# TTN-Node-v7-01.net
KiCad netlist of a schematic drawn in EAGLE
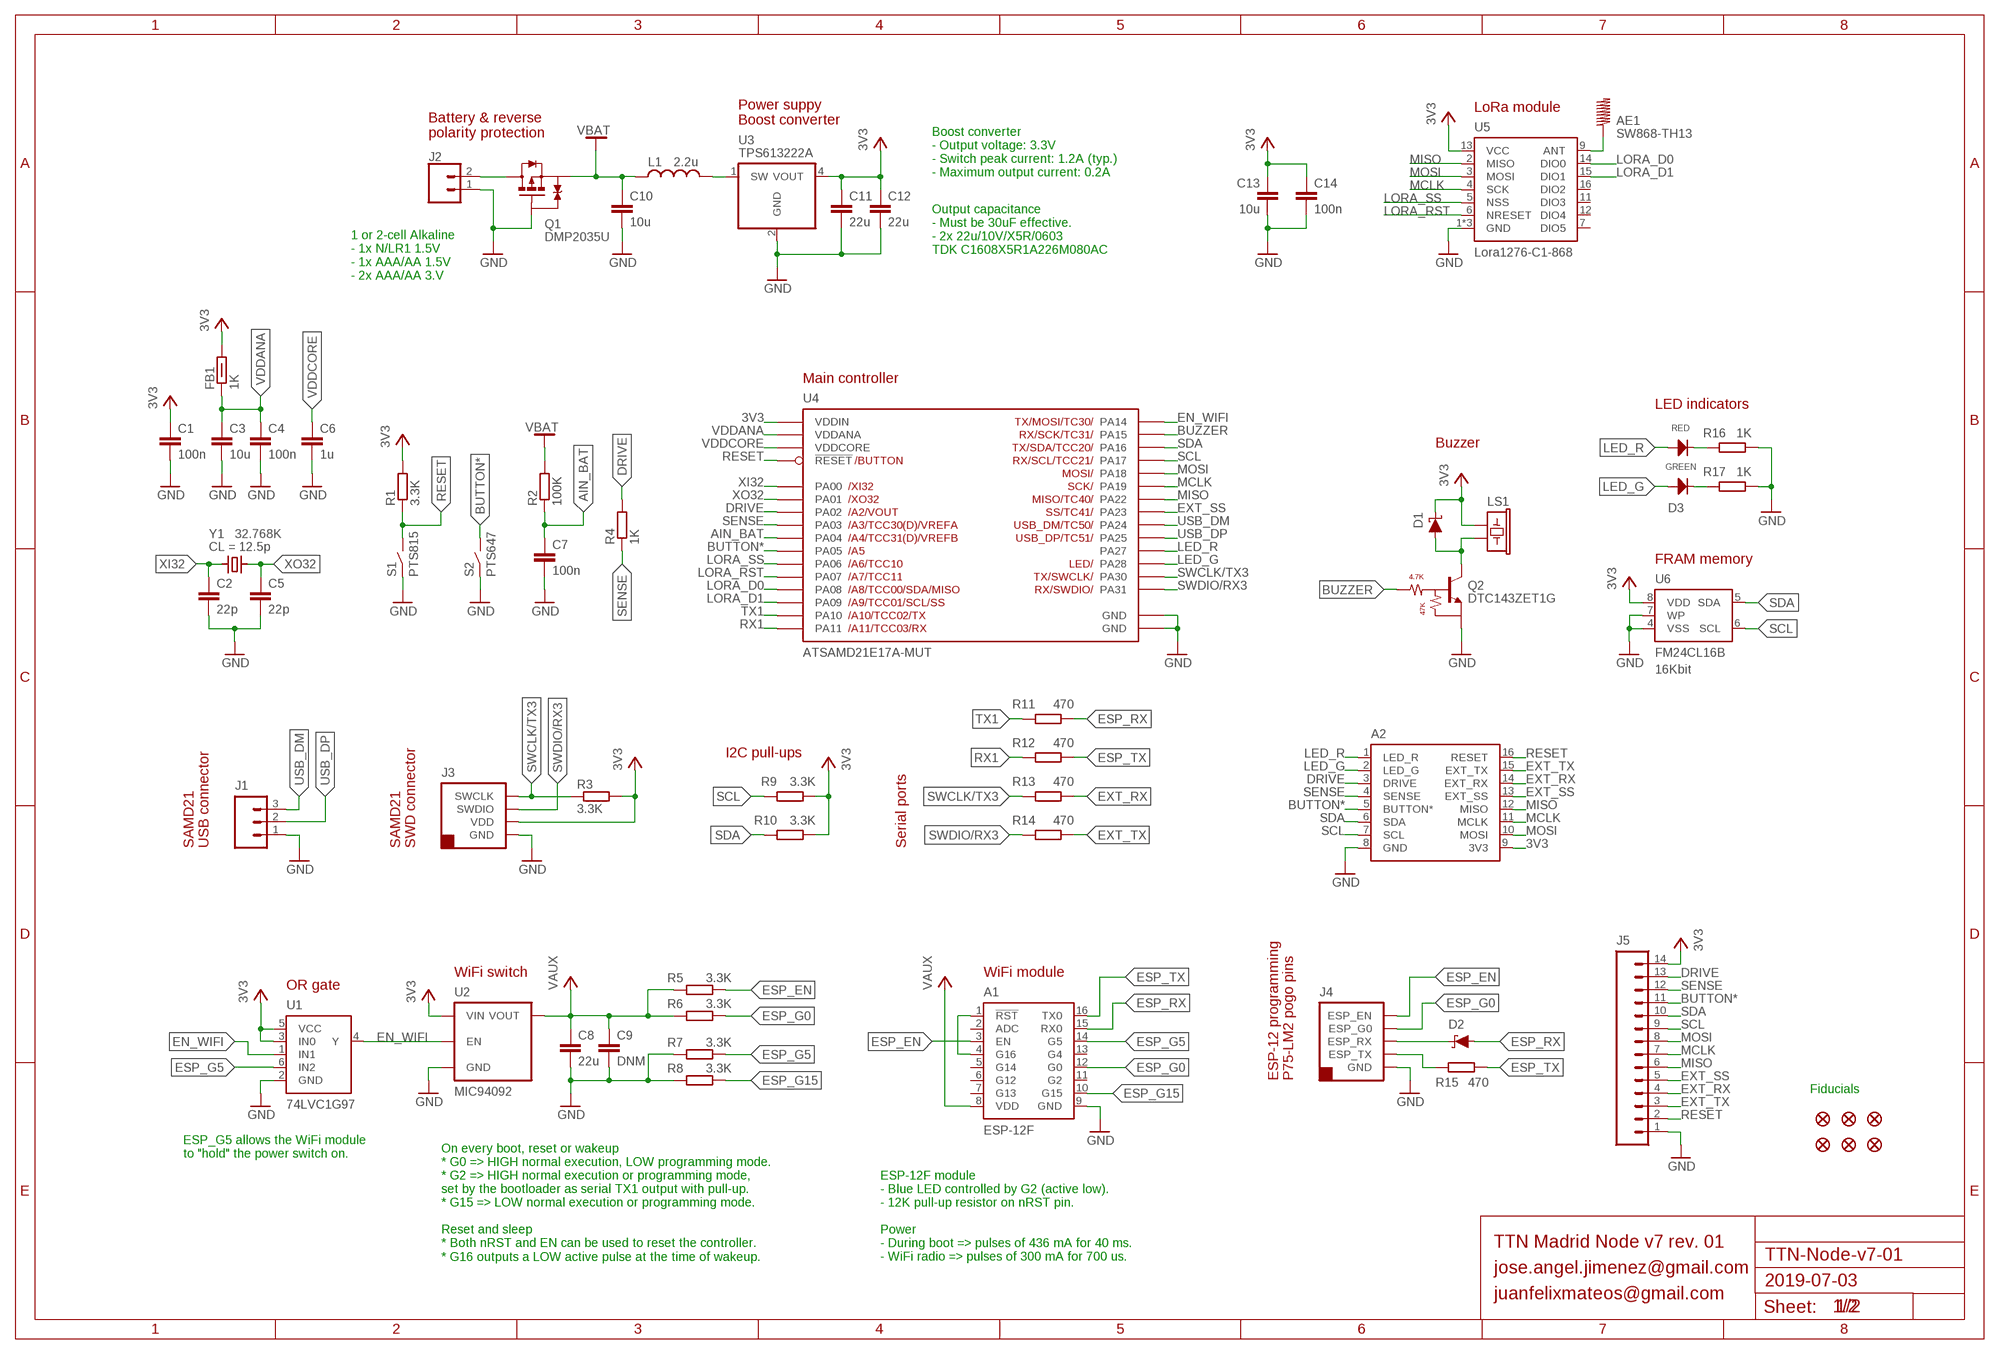
[diagram p0: schematic, sheet 1]
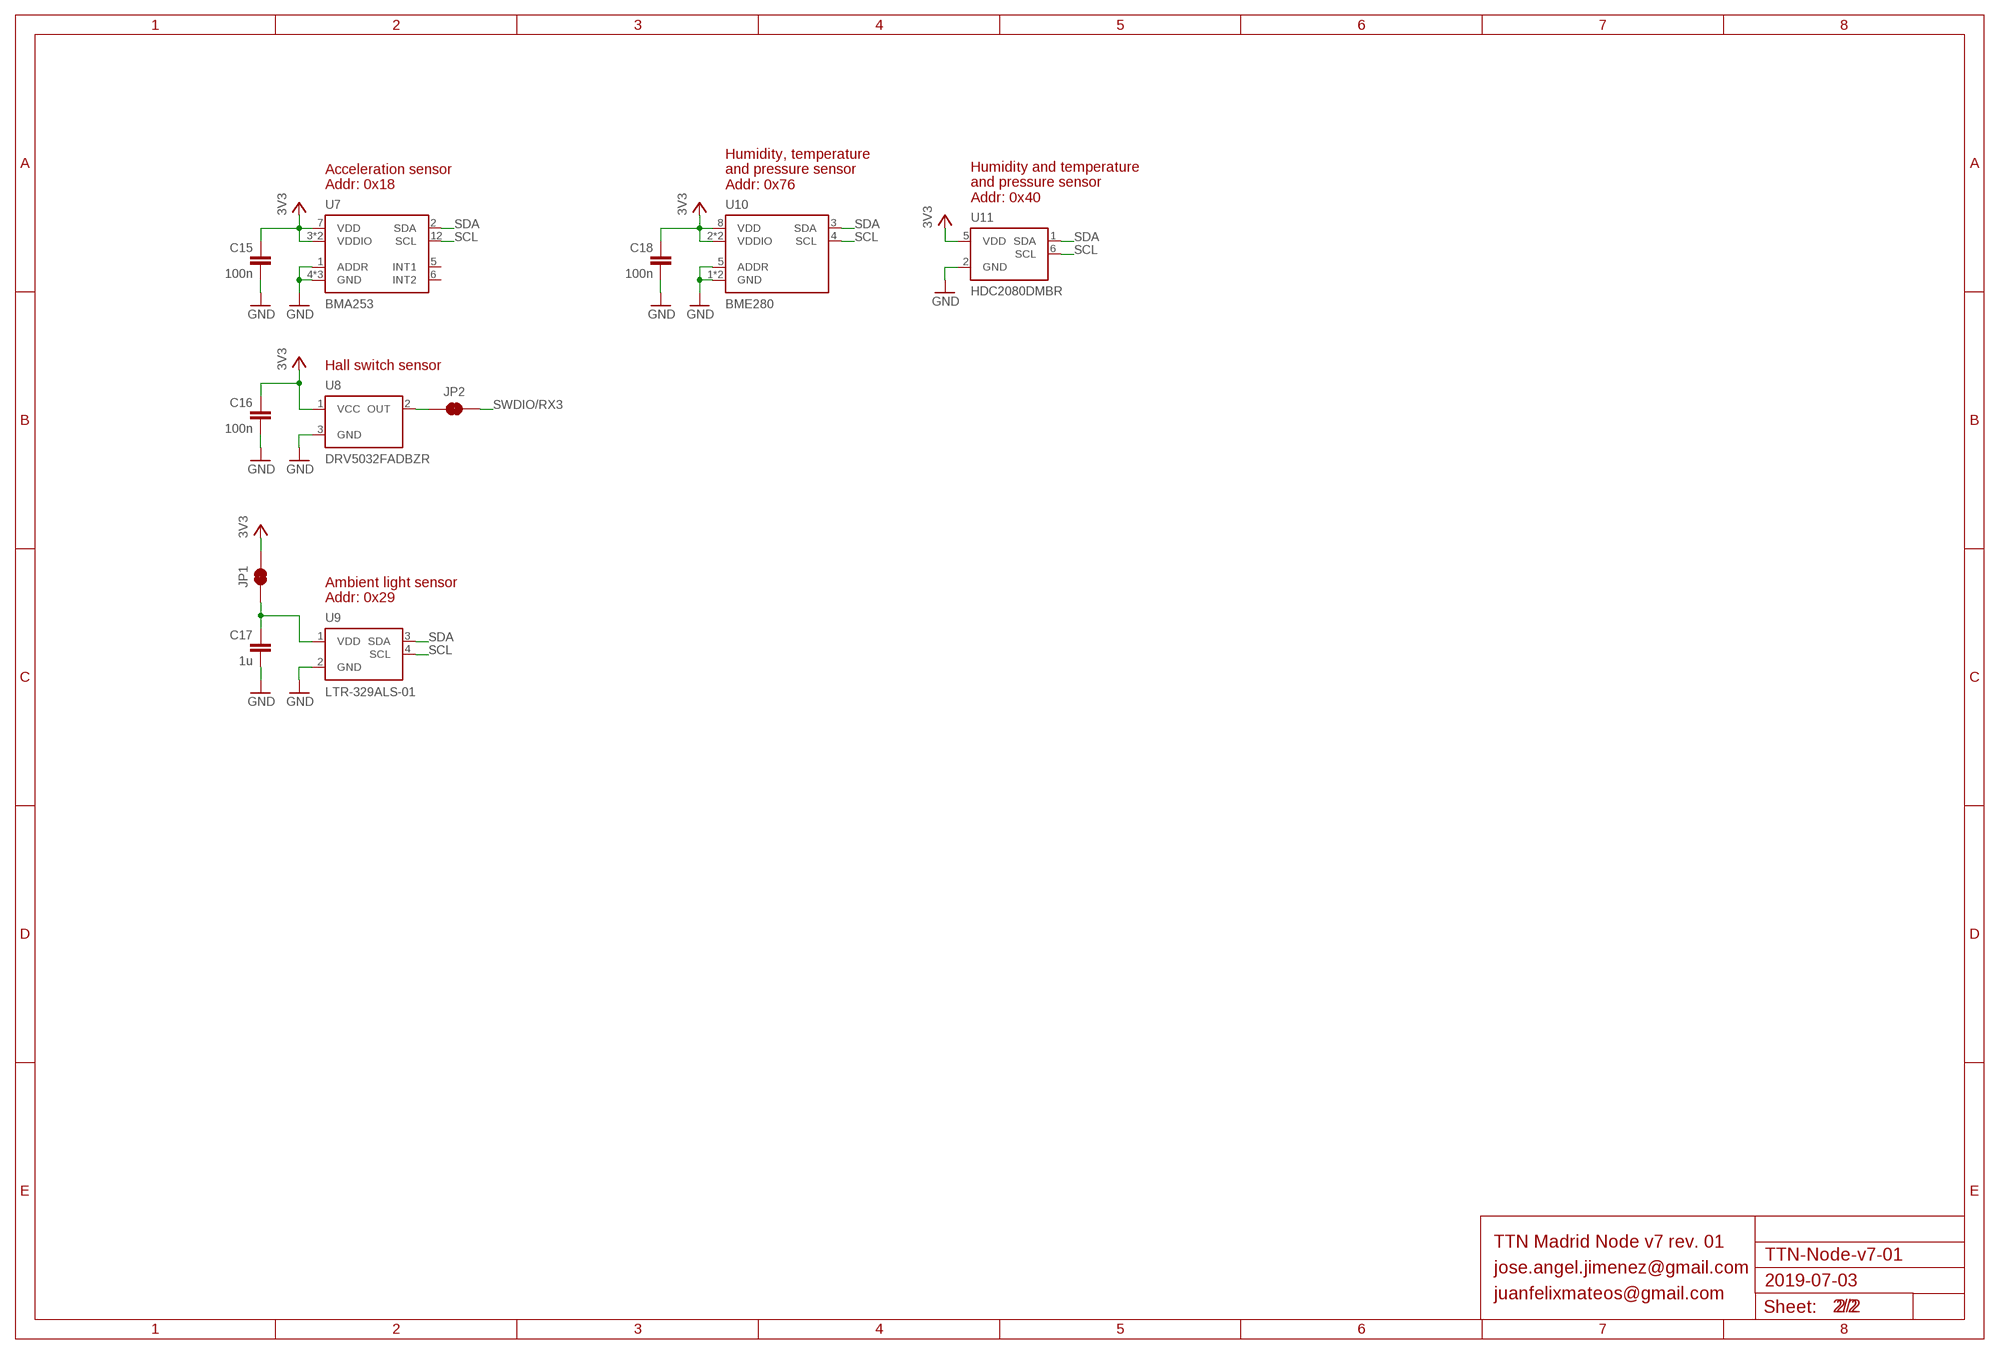
[diagram p1: schematic, sheet 2]

(export (version "E")
  (design (tool "Eeschema 10.0.6"))
  (components
    (comp (ref "A1")
      (value "ESP-12F")
      (footprint "eagle-import:ESP-12")
      (libsource (lib "eagle-import") (part "ESP-12F"))
    )
    (comp (ref "A2")
      (value "TTN_MAD_NODE_V7_EXP")
      (footprint "eagle-import:TTN_MAD_NODE_V7_EXP")
      (libsource (lib "eagle-import") (part "TTN_MAD_NODE_V7_EXP"))
    )
    (comp (ref "AE1")
      (value "SW868-TH13")
      (footprint "eagle-import:ANT-SW868-TH13")
      (fields (field (name "MFR") "NiceRF"))
      (libsource (lib "eagle-import") (part "ANT-SW868-TH13"))
    )
    (comp (ref "C1")
      (value "100n")
      (footprint "eagle-import:C0603")
      (fields
        (field (name "DIELECTRIC") "X7R")
        (field (name "MFR") "Yageo")
        (field (name "MPN") "CC0603KRX7R9BB104")
        (field (name "TOLERANCE") "10%")
        (field (name "VOLTAGE") "50V")
      )
      (libsource (lib "eagle-import") (part "CAPACITOR_0603"))
    )
    (comp (ref "C2")
      (value "22p")
      (footprint "eagle-import:C0603")
      (fields
        (field (name "DIELECTRIC") "C0G")
        (field (name "MFR") "AVX")
        (field (name "MPN") "06035A220JAT2A")
        (field (name "TOLERANCE") "5%")
        (field (name "VOLTAGE") "50V")
      )
      (libsource (lib "eagle-import") (part "CAPACITOR_0603"))
    )
    (comp (ref "C3")
      (value "10u")
      (footprint "eagle-import:C0603")
      (fields
        (field (name "DIELECTRIC") "X5R")
        (field (name "MFR") "Murata")
        (field (name "MPN") "GRM188R60J106KE47D")
        (field (name "TOLERANCE") "10%")
        (field (name "VOLTAGE") "6.3V")
      )
      (libsource (lib "eagle-import") (part "CAPACITOR_0603"))
    )
    (comp (ref "C4")
      (value "100n")
      (footprint "eagle-import:C0603")
      (fields
        (field (name "DIELECTRIC") "X7R")
        (field (name "MFR") "Yageo")
        (field (name "MPN") "CC0603KRX7R9BB104")
        (field (name "TOLERANCE") "10%")
        (field (name "VOLTAGE") "50V")
      )
      (libsource (lib "eagle-import") (part "CAPACITOR_0603"))
    )
    (comp (ref "C5")
      (value "22p")
      (footprint "eagle-import:C0603")
      (fields
        (field (name "DIELECTRIC") "C0G")
        (field (name "MFR") "AVX")
        (field (name "MPN") "06035A220JAT2A")
        (field (name "TOLERANCE") "5%")
        (field (name "VOLTAGE") "50V")
      )
      (libsource (lib "eagle-import") (part "CAPACITOR_0603"))
    )
    (comp (ref "C6")
      (value "1u")
      (footprint "eagle-import:C0603")
      (fields
        (field (name "DIELECTRIC") "X5R")
        (field (name "MFR") "Yageo")
        (field (name "MPN") "CC0603KRX5R8BB105")
        (field (name "TOLERANCE") "10%")
        (field (name "VOLTAGE") "25V")
      )
      (libsource (lib "eagle-import") (part "CAPACITOR_0603"))
    )
    (comp (ref "C7")
      (value "100n")
      (footprint "eagle-import:C0603")
      (fields
        (field (name "DIELECTRIC") "X7R")
        (field (name "MFR") "Yageo")
        (field (name "MPN") "CC0603KRX7R9BB104")
        (field (name "TOLERANCE") "10%")
        (field (name "VOLTAGE") "50V")
      )
      (libsource (lib "eagle-import") (part "CAPACITOR_0603"))
    )
    (comp (ref "C8")
      (value "22u")
      (footprint "eagle-import:C0603")
      (fields
        (field (name "DIELECTRIC") "X5R")
        (field (name "MFR") "TDK")
        (field (name "MPN") "C1608X5R1A226M080AC")
        (field (name "TOLERANCE") "20%")
        (field (name "VOLTAGE") "10V")
      )
      (libsource (lib "eagle-import") (part "CAPACITOR_0603"))
    )
    (comp (ref "C9")
      (value "DNM")
      (footprint "eagle-import:C0603")
      (fields
        (field (name "DIELECTRIC") "X5R")
        (field (name "MFR") "TDK")
        (field (name "MPN") "C1608X5R1A226M080AC")
        (field (name "POPULATE") "0")
        (field (name "TOLERANCE") "20%")
        (field (name "VOLTAGE") "10V")
      )
      (libsource (lib "eagle-import") (part "CAPACITOR_0603"))
    )
    (comp (ref "C10")
      (value "10u")
      (footprint "eagle-import:C0603")
      (fields
        (field (name "DIELECTRIC") "X5R")
        (field (name "MFR") "Murata")
        (field (name "MPN") "GRM188R60J106KE47D")
        (field (name "TOLERANCE") "10%")
        (field (name "VOLTAGE") "6.3V")
      )
      (libsource (lib "eagle-import") (part "CAPACITOR_0603"))
    )
    (comp (ref "C11")
      (value "22u")
      (footprint "eagle-import:C0603")
      (fields
        (field (name "DIELECTRIC") "X5R")
        (field (name "MFR") "TDK")
        (field (name "MPN") "C1608X5R1A226M080AC")
        (field (name "TOLERANCE") "20%")
        (field (name "VOLTAGE") "10V")
      )
      (libsource (lib "eagle-import") (part "CAPACITOR_0603"))
    )
    (comp (ref "C12")
      (value "22u")
      (footprint "eagle-import:C0603")
      (fields
        (field (name "DIELECTRIC") "X5R")
        (field (name "MFR") "TDK")
        (field (name "MPN") "C1608X5R1A226M080AC")
        (field (name "TOLERANCE") "20%")
        (field (name "VOLTAGE") "10V")
      )
      (libsource (lib "eagle-import") (part "CAPACITOR_0603"))
    )
    (comp (ref "C13")
      (value "10u")
      (footprint "eagle-import:C0603")
      (fields
        (field (name "DIELECTRIC") "X5R")
        (field (name "MFR") "Murata")
        (field (name "MPN") "GRM188R60J106KE47D")
        (field (name "TOLERANCE") "10%")
        (field (name "VOLTAGE") "6.3V")
      )
      (libsource (lib "eagle-import") (part "CAPACITOR_0603"))
    )
    (comp (ref "C14")
      (value "100n")
      (footprint "eagle-import:C0603")
      (fields
        (field (name "DIELECTRIC") "X7R")
        (field (name "MFR") "Yageo")
        (field (name "MPN") "CC0603KRX7R9BB104")
        (field (name "TOLERANCE") "10%")
        (field (name "VOLTAGE") "50V")
      )
      (libsource (lib "eagle-import") (part "CAPACITOR_0603"))
    )
    (comp (ref "D1")
      (value "RB521S30")
      (footprint "eagle-import:SOD523")
      (fields (field (name "MFR") "On Semi") (field (name "MPN") "RB521S30T1G"))
      (libsource (lib "eagle-import") (part "DIODE-SCHOTTKY-RB521S30T1G"))
    )
    (comp (ref "D2")
      (value "RB521S30")
      (footprint "eagle-import:SOD523")
      (fields (field (name "MFR") "On Semi") (field (name "MPN") "RB521S30T1G"))
      (libsource (lib "eagle-import") (part "DIODE-SCHOTTKY-RB521S30T1G"))
    )
    (comp (ref "D3")
      (value "LTST-E682KRKGWT")
      (footprint "eagle-import:LED-PLCC-4-3522")
      (fields (field (name "MFR") "Lite-On"))
      (libsource (lib "eagle-import") (part "LED-RG-LTST-E682KRKGWT"))
    )
    (comp (ref "FB1")
      (value "1K")
      (footprint "eagle-import:L0603")
      (fields (field (name "MFR") "TDK") (field (name "MPN") "MPZ1608S102ATA00"))
      (libsource (lib "eagle-import") (part "FERRITE_BEAD_0603_1K"))
    )
    (comp (ref "FD1")
      (value "FIDUCIAL1X2")
      (footprint "eagle-import:FIDUCIAL-1X2")
      (libsource (lib "eagle-import") (part "FIDUCIAL1X2"))
    )
    (comp (ref "FD2")
      (value "FIDUCIAL1X2")
      (footprint "eagle-import:FIDUCIAL-1X2")
      (libsource (lib "eagle-import") (part "FIDUCIAL1X2"))
    )
    (comp (ref "FD3")
      (value "FIDUCIAL1X2")
      (footprint "eagle-import:FIDUCIAL-1X2")
      (libsource (lib "eagle-import") (part "FIDUCIAL1X2"))
    )
    (comp (ref "FD4")
      (value "FIDUCIAL1X2")
      (footprint "eagle-import:FIDUCIAL-1X2")
      (libsource (lib "eagle-import") (part "FIDUCIAL1X2"))
    )
    (comp (ref "FD5")
      (value "FIDUCIAL1X2")
      (footprint "eagle-import:FIDUCIAL-1X2")
      (libsource (lib "eagle-import") (part "FIDUCIAL1X2"))
    )
    (comp (ref "FD6")
      (value "FIDUCIAL1X2")
      (footprint "eagle-import:FIDUCIAL-1X2")
      (libsource (lib "eagle-import") (part "FIDUCIAL1X2"))
    )
    (comp (ref "J1")
      (value "USB")
      (footprint "eagle-import:1X03")
      (libsource (lib "eagle-import") (part "CONN_03"))
    )
    (comp (ref "J2")
      (value "CONN_02")
      (footprint "eagle-import:1X02")
      (libsource (lib "eagle-import") (part "CONN_02"))
    )
    (comp (ref "J3")
      (value "CON-SWD-HDR-1X4-254")
      (footprint "eagle-import:HDR-1X4-254-SWD")
      (libsource (lib "eagle-import") (part "CON-SWD-HDR-1X4-254"))
    )
    (comp (ref "J4")
      (value "CON-ESP-HDR-1X5-254")
      (footprint "eagle-import:HDR-1X5-254-ESP")
      (libsource (lib "eagle-import") (part "CON-ESP-HDR-1X5-254"))
    )
    (comp (ref "J5")
      (value "CONN_14")
      (footprint "eagle-import:1X14")
      (libsource (lib "eagle-import") (part "CONN_14"))
    )
    (comp (ref "L1")
      (value "2.2u")
      (footprint "eagle-import:L2520_MM")
      (fields
        (field (name "MFR") "Bourns")
        (field (name "MPN") "SRN2512-2R2M")
        (field (name "PN1") "652-SRN2512-2R2M")
        (field (name "SUPPLIER1") "Mouser")
      )
      (libsource (lib "eagle-import") (part "INDUCTOR_2520_MM"))
    )
    (comp (ref "LS1")
      (value "BUZZER-SMD-4030_MM")
      (footprint "eagle-import:BUZZER-4030_MM")
      (fields (field (name "MFR") "AAC") (field (name "MPN") "DET402-G-1"))
      (libsource (lib "eagle-import") (part "BUZZER-SMD-4030_MM"))
    )
    (comp (ref "Q1")
      (value "DMP2035U")
      (footprint "eagle-import:SOT23-3")
      (fields (field (name "MFR") "Diodes") (field (name "MPN") "DMP2035U-7"))
      (libsource (lib "eagle-import") (part "MOSFET-P-DMP2035U-ESD"))
    )
    (comp (ref "Q2")
      (value "DTC143ZET1G")
      (footprint "eagle-import:SC75-3")
      (fields (field (name "MFR") "On Semi"))
      (libsource (lib "eagle-import") (part "BJT-NPN-4.7K-47K"))
    )
    (comp (ref "R1")
      (value "3.3K")
      (footprint "eagle-import:R0603")
      (fields (field (name "TOLERANCE") "1%"))
      (libsource (lib "eagle-import") (part "RESISTOR_0603"))
    )
    (comp (ref "R2")
      (value "100K")
      (footprint "eagle-import:R0603")
      (fields (field (name "TOLERANCE") "1%"))
      (libsource (lib "eagle-import") (part "RESISTOR_0603"))
    )
    (comp (ref "R3")
      (value "3.3K")
      (footprint "eagle-import:R0603")
      (fields (field (name "TOLERANCE") "1%"))
      (libsource (lib "eagle-import") (part "RESISTOR_0603"))
    )
    (comp (ref "R4")
      (value "1K")
      (footprint "eagle-import:R0603")
      (fields (field (name "TOLERANCE") "1%"))
      (libsource (lib "eagle-import") (part "RESISTOR_0603"))
    )
    (comp (ref "R5")
      (value "3.3K")
      (footprint "eagle-import:R0603")
      (libsource (lib "eagle-import") (part "RESISTOR_0603"))
    )
    (comp (ref "R6")
      (value "3.3K")
      (footprint "eagle-import:R0603")
      (libsource (lib "eagle-import") (part "RESISTOR_0603"))
    )
    (comp (ref "R7")
      (value "3.3K")
      (footprint "eagle-import:R0603")
      (libsource (lib "eagle-import") (part "RESISTOR_0603"))
    )
    (comp (ref "R8")
      (value "3.3K")
      (footprint "eagle-import:R0603")
      (libsource (lib "eagle-import") (part "RESISTOR_0603"))
    )
    (comp (ref "R9")
      (value "3.3K")
      (footprint "eagle-import:R0603")
      (fields (field (name "TOLERANCE") "1%"))
      (libsource (lib "eagle-import") (part "RESISTOR_0603"))
    )
    (comp (ref "R10")
      (value "3.3K")
      (footprint "eagle-import:R0603")
      (fields (field (name "TOLERANCE") "1%"))
      (libsource (lib "eagle-import") (part "RESISTOR_0603"))
    )
    (comp (ref "R11")
      (value "470")
      (footprint "eagle-import:R0603")
      (fields (field (name "TOLERANCE") "1%"))
      (libsource (lib "eagle-import") (part "RESISTOR_0603"))
    )
    (comp (ref "R12")
      (value "470")
      (footprint "eagle-import:R0603")
      (fields (field (name "TOLERANCE") "1%"))
      (libsource (lib "eagle-import") (part "RESISTOR_0603"))
    )
    (comp (ref "R13")
      (value "470")
      (footprint "eagle-import:R0603")
      (fields (field (name "TOLERANCE") "1%"))
      (libsource (lib "eagle-import") (part "RESISTOR_0603"))
    )
    (comp (ref "R14")
      (value "470")
      (footprint "eagle-import:R0603")
      (fields (field (name "TOLERANCE") "1%"))
      (libsource (lib "eagle-import") (part "RESISTOR_0603"))
    )
    (comp (ref "R15")
      (value "470")
      (footprint "eagle-import:R0603")
      (libsource (lib "eagle-import") (part "RESISTOR_0603"))
    )
    (comp (ref "R16")
      (value "1K")
      (footprint "eagle-import:R0603")
      (libsource (lib "eagle-import") (part "RESISTOR_0603"))
    )
    (comp (ref "R17")
      (value "1K")
      (footprint "eagle-import:R0603")
      (libsource (lib "eagle-import") (part "RESISTOR_0603"))
    )
    (comp (ref "S1")
      (value "PTS815")
      (footprint "eagle-import:SW-SMD-PTS815-4232")
      (fields (field (name "MFR") "C&K") (field (name "MPN") "PTS815 SJM 250 SMTR LFS"))
      (libsource (lib "eagle-import") (part "SW-PTS810/815-PTS815"))
    )
    (comp (ref "S2")
      (value "PTS647")
      (footprint "eagle-import:SW-SMD-PTS647-4545")
      (fields (field (name "MFR") "C&K") (field (name "MPN") "PTS647SK50SMTR2LFS"))
      (libsource (lib "eagle-import") (part "SW-PTS647-2.5N-5.0MM"))
    )
    (comp (ref "U1")
      (value "74LVC1G97")
      (footprint "eagle-import:SC70-6")
      (fields (field (name "MFR") "TI") (field (name "MPN") "SN74LVC1G97DCKR"))
      (libsource (lib "eagle-import") (part "LOGIC-1G97DCKR"))
    )
    (comp (ref "U2")
      (value "MIC94092")
      (footprint "eagle-import:SOT363")
      (fields (field (name "MFR") "Microchip") (field (name "MPN") "MIC94092YC6-TR"))
      (libsource (lib "eagle-import") (part "MIC94092YC6-TR"))
    )
    (comp (ref "U3")
      (value "TPS613222A")
      (footprint "eagle-import:SOT23-5")
      (fields (field (name "MFR") "Texas Instruments") (field (name "MPN") "TPS613222ADBVR"))
      (libsource (lib "eagle-import") (part "VREG-TPS613222ADBVR"))
    )
    (comp (ref "U4")
      (value "ATSAMD21E17A-MUT")
      (footprint "eagle-import:VQFN32L-05-5050_MM-SEGMENTED")
      (libsource (lib "eagle-import") (part "SAMD21E_A/B/C/D-QFN32L"))
    )
    (comp (ref "U5")
      (value "Lora1276-C1-868")
      (footprint "eagle-import:RFM95W")
      (fields (field (name "MFR") "NiceRF"))
      (libsource (lib "eagle-import") (part "LORA-RFM95W-LORA1276-C1-868"))
    )
    (comp (ref "U6")
      (value "FM24CL16B")
      (footprint "eagle-import:SO8")
      (fields
        (field (name "MFR") "Cypress")
        (field (name "MPN") "FM24CL16B-GTR")
        (field (name "SIZE") "16Kbit")
      )
      (libsource (lib "eagle-import") (part "MEMORY-I2C-WP-FM24CL16B-G"))
    )
    (comp (ref "Y1")
      (value "32.768K")
      (footprint "eagle-import:CRYSTAL-3215")
      (fields
        (field (name "CL") "12.5p")
        (field (name "MFR") "Epson")
        (field (name "MPN") "FC-135 32.7680KA-A3")
        (field (name "PN1") "732-FC135-32.76KAA3")
      )
      (libsource (lib "eagle-import") (part "CRYSTAL-3215"))
    )
    (comp (ref "C15")
      (value "100n")
      (footprint "eagle-import:C0603")
      (fields
        (field (name "DIELECTRIC") "X7R")
        (field (name "MFR") "Yageo")
        (field (name "MPN") "CC0603KRX7R9BB104")
        (field (name "TOLERANCE") "10%")
        (field (name "VOLTAGE") "50V")
      )
      (libsource (lib "eagle-import") (part "CAPACITOR_0603"))
    )
    (comp (ref "C16")
      (value "100n")
      (footprint "eagle-import:C0603")
      (fields
        (field (name "DIELECTRIC") "X7R")
        (field (name "MFR") "Yageo")
        (field (name "MPN") "CC0603KRX7R9BB104")
        (field (name "TOLERANCE") "10%")
        (field (name "VOLTAGE") "50V")
      )
      (libsource (lib "eagle-import") (part "CAPACITOR_0603"))
    )
    (comp (ref "C17")
      (value "1u")
      (footprint "eagle-import:C0603")
      (fields
        (field (name "DIELECTRIC") "X5R")
        (field (name "MFR") "Yageo")
        (field (name "MPN") "CC0603KRX5R8BB105")
        (field (name "TOLERANCE") "10%")
        (field (name "VOLTAGE") "25V")
      )
      (libsource (lib "eagle-import") (part "CAPACITOR_0603"))
    )
    (comp (ref "C18")
      (value "100n")
      (footprint "eagle-import:C0603")
      (fields
        (field (name "DIELECTRIC") "X7R")
        (field (name "MFR") "Yageo")
        (field (name "MPN") "CC0603KRX7R9BB104")
        (field (name "TOLERANCE") "10%")
        (field (name "VOLTAGE") "50V")
      )
      (libsource (lib "eagle-import") (part "CAPACITOR_0603"))
    )
    (comp (ref "JP1")
      (value "JUMPER-SMT_2_NC_TRACE-OUTLINE")
      (footprint "eagle-import:SMT-JUMPER_2_NC_TRACE_OUTLINE")
      (libsource (lib "eagle-import") (part "JUMPER-SMT_2_NC_TRACE-OUTLINE"))
    )
    (comp (ref "JP2")
      (value "JUMPER-SMT_2_NC_TRACE-OUTLINE")
      (footprint "eagle-import:SMT-JUMPER_2_NC_TRACE_OUTLINE")
      (libsource (lib "eagle-import") (part "JUMPER-SMT_2_NC_TRACE-OUTLINE"))
    )
    (comp (ref "U7")
      (value "BMA253")
      (footprint "eagle-import:LGA12")
      (libsource (lib "eagle-import") (part "SENSOR-BMA253-I2C"))
    )
    (comp (ref "U8")
      (value "DRV5032FADBZR")
      (footprint "eagle-import:SOT23-3")
      (libsource (lib "eagle-import") (part "SENSOR-DRV5032"))
    )
    (comp (ref "U9")
      (value "LTR-329ALS-01")
      (footprint "eagle-import:CHIPLED-PLCC4-2020MM")
      (libsource (lib "eagle-import") (part "SENSOR-LTR-329ALS-01"))
    )
    (comp (ref "U10")
      (value "BME280")
      (footprint "eagle-import:BME280")
      (libsource (lib "eagle-import") (part "SENSOR-BME280-I2C"))
    )
    (comp (ref "U11")
      (value "HDC2080DMBR")
      (footprint "eagle-import:WSON-6-NOPAD")
      (libsource (lib "eagle-import") (part "SENSOR-HDC1080"))
    )
  )
  (nets
    (net (code "1") (name "3V3") (class "Default")
      (node (ref "A2") (pin "9") (pinfunction "3V3_9") (pintype "passive"))
      (node (ref "C1") (pin "P$1") (pinfunction "1_P$1") (pintype "passive"))
      (node (ref "C11") (pin "P$1") (pinfunction "1_P$1") (pintype "passive"))
      (node (ref "C12") (pin "P$1") (pinfunction "1_P$1") (pintype "passive"))
      (node (ref "C13") (pin "P$1") (pinfunction "1_P$1") (pintype "passive"))
      (node (ref "C14") (pin "P$1") (pinfunction "1_P$1") (pintype "passive"))
      (node (ref "C15") (pin "P$1") (pinfunction "1_P$1") (pintype "passive"))
      (node (ref "C16") (pin "P$1") (pinfunction "1_P$1") (pintype "passive"))
      (node (ref "C18") (pin "P$1") (pinfunction "1_P$1") (pintype "passive"))
      (node (ref "D1") (pin "C") (pinfunction "C_C") (pintype "passive"))
      (node (ref "FB1") (pin "P$2") (pinfunction "2_P$2") (pintype "passive"))
      (node (ref "J3") (pin "2") (pinfunction "VDD_2") (pintype "power_in"))
      (node (ref "J5") (pin "14") (pinfunction "14_14") (pintype "passive"))
      (node (ref "JP1") (pin "2") (pinfunction "2_2") (pintype "passive"))
      (node (ref "LS1") (pin "1") (pinfunction "1_1") (pintype "passive"))
      (node (ref "R1") (pin "P$2") (pinfunction "2_P$2") (pintype "passive"))
      (node (ref "R10") (pin "P$2") (pinfunction "2_P$2") (pintype "passive"))
      (node (ref "R3") (pin "P$2") (pinfunction "2_P$2") (pintype "passive"))
      (node (ref "R9") (pin "P$2") (pinfunction "2_P$2") (pintype "passive"))
      (node (ref "U1") (pin "3") (pinfunction "IN0_3") (pintype "input"))
      (node (ref "U1") (pin "5") (pinfunction "VCC_5") (pintype "power_in"))
      (node (ref "U10") (pin "2") (pinfunction "VDDIO_2") (pintype "passive"))
      (node (ref "U10") (pin "6") (pinfunction "VDDIO_6") (pintype "passive"))
      (node (ref "U10") (pin "8") (pinfunction "VDD_8") (pintype "passive"))
      (node (ref "U11") (pin "5") (pinfunction "VDD_5") (pintype "power_in"))
      (node (ref "U2") (pin "4") (pinfunction "VIN_4") (pintype "power_in"))
      (node (ref "U3") (pin "4") (pinfunction "VOUT_4") (pintype "power_in"))
      (node (ref "U4") (pin "30") (pinfunction "VDDIN_30") (pintype "power_in"))
      (node (ref "U5") (pin "13") (pinfunction "VCC_13") (pintype "power_in"))
      (node (ref "U6") (pin "8") (pinfunction "VDD_8") (pintype "power_in"))
      (node (ref "U7") (pin "11") (pinfunction "VDDIO_11") (pintype "passive"))
      (node (ref "U7") (pin "3") (pinfunction "VDDIO_3") (pintype "passive"))
      (node (ref "U7") (pin "7") (pinfunction "VDD_7") (pintype "passive"))
      (node (ref "U8") (pin "1") (pinfunction "VCC_1") (pintype "passive"))
    )
    (net (code "2") (name "AIN_BAT") (class "Default")
      (node (ref "C7") (pin "P$1") (pinfunction "1_P$1") (pintype "passive"))
      (node (ref "R2") (pin "P$1") (pinfunction "1_P$1") (pintype "passive"))
      (node (ref "U4") (pin "5") (pinfunction "PA04_5") (pintype "bidirectional"))
    )
    (net (code "3") (name "BUTTON*") (class "Default")
      (node (ref "A2") (pin "5") (pinfunction "BUTTON*_5") (pintype "bidirectional"))
      (node (ref "J5") (pin "11") (pinfunction "11_11") (pintype "passive"))
      (node (ref "S2") (pin "3") (pinfunction "2_3") (pintype "bidirectional"))
      (node (ref "S2") (pin "4") (pinfunction "2_4") (pintype "bidirectional"))
      (node (ref "U4") (pin "6") (pinfunction "PA05_6") (pintype "bidirectional"))
    )
    (net (code "4") (name "BUZZER") (class "Default")
      (node (ref "Q2") (pin "1") (pinfunction "B_1") (pintype "passive"))
      (node (ref "U4") (pin "16") (pinfunction "PA15_16") (pintype "bidirectional"))
    )
    (net (code "5") (name "DRIVE") (class "Default")
      (node (ref "A2") (pin "3") (pinfunction "DRIVE_3") (pintype "bidirectional"))
      (node (ref "J5") (pin "13") (pinfunction "13_13") (pintype "passive"))
      (node (ref "R4") (pin "P$2") (pinfunction "2_P$2") (pintype "passive"))
      (node (ref "U4") (pin "3") (pinfunction "PA02_3") (pintype "bidirectional"))
    )
    (net (code "6") (name "EN_WIFI") (class "Default")
      (node (ref "U1") (pin "1") (pinfunction "IN1_1") (pintype "input"))
      (node (ref "U1") (pin "4") (pinfunction "Y_4") (pintype "bidirectional"))
      (node (ref "U2") (pin "6") (pinfunction "EN_6") (pintype "input"))
      (node (ref "U4") (pin "15") (pinfunction "PA14_15") (pintype "bidirectional"))
    )
    (net (code "7") (name "ESP_EN") (class "Default")
      (node (ref "A1") (pin "3") (pinfunction "EN_3") (pintype "bidirectional"))
      (node (ref "J4") (pin "5") (pinfunction "ESP_EN_5") (pintype "output"))
      (node (ref "R5") (pin "P$2") (pinfunction "2_P$2") (pintype "passive"))
    )
    (net (code "8") (name "ESP_G0") (class "Default")
      (node (ref "A1") (pin "12") (pinfunction "G0_12") (pintype "bidirectional"))
      (node (ref "J4") (pin "4") (pinfunction "ESP_G0_4") (pintype "output"))
      (node (ref "R6") (pin "P$2") (pinfunction "2_P$2") (pintype "passive"))
    )
    (net (code "9") (name "ESP_G5") (class "Default")
      (node (ref "A1") (pin "14") (pinfunction "G5_14") (pintype "bidirectional"))
      (node (ref "R7") (pin "P$2") (pinfunction "2_P$2") (pintype "passive"))
      (node (ref "U1") (pin "6") (pinfunction "IN2_6") (pintype "input"))
    )
    (net (code "10") (name "ESP_G15") (class "Default")
      (node (ref "A1") (pin "10") (pinfunction "G15_10") (pintype "bidirectional"))
      (node (ref "R8") (pin "P$2") (pinfunction "2_P$2") (pintype "passive"))
    )
    (net (code "11") (name "ESP_RX") (class "Default")
      (node (ref "A1") (pin "15") (pinfunction "RX0_15") (pintype "bidirectional"))
      (node (ref "D2") (pin "A") (pinfunction "A_A") (pintype "passive"))
      (node (ref "R11") (pin "P$2") (pinfunction "2_P$2") (pintype "passive"))
    )
    (net (code "12") (name "ESP_TX") (class "Default")
      (node (ref "A1") (pin "16") (pinfunction "TX0_16") (pintype "bidirectional"))
      (node (ref "R12") (pin "P$2") (pinfunction "2_P$2") (pintype "passive"))
      (node (ref "R15") (pin "P$2") (pinfunction "2_P$2") (pintype "passive"))
    )
    (net (code "13") (name "EXT_RX") (class "Default")
      (node (ref "A2") (pin "14") (pinfunction "EXT_RX_14") (pintype "bidirectional"))
      (node (ref "J5") (pin "4") (pinfunction "4_4") (pintype "passive"))
      (node (ref "R13") (pin "P$2") (pinfunction "2_P$2") (pintype "passive"))
    )
    (net (code "14") (name "EXT_SS") (class "Default")
      (node (ref "A2") (pin "13") (pinfunction "EXT_SS_13") (pintype "bidirectional"))
      (node (ref "J5") (pin "5") (pinfunction "5_5") (pintype "passive"))
      (node (ref "U4") (pin "22") (pinfunction "PA23_22") (pintype "bidirectional"))
    )
    (net (code "15") (name "EXT_TX") (class "Default")
      (node (ref "A2") (pin "15") (pinfunction "EXT_TX_15") (pintype "bidirectional"))
      (node (ref "J5") (pin "3") (pinfunction "3_3") (pintype "passive"))
      (node (ref "R14") (pin "P$2") (pinfunction "2_P$2") (pintype "passive"))
    )
    (net (code "16") (name "GND") (class "Default")
      (node (ref "A1") (pin "9") (pinfunction "GND_9") (pintype "bidirectional"))
      (node (ref "A2") (pin "8") (pinfunction "GND_8") (pintype "passive"))
      (node (ref "C1") (pin "P$2") (pinfunction "2_P$2") (pintype "passive"))
      (node (ref "C10") (pin "P$2") (pinfunction "2_P$2") (pintype "passive"))
      (node (ref "C11") (pin "P$2") (pinfunction "2_P$2") (pintype "passive"))
      (node (ref "C12") (pin "P$2") (pinfunction "2_P$2") (pintype "passive"))
      (node (ref "C13") (pin "P$2") (pinfunction "2_P$2") (pintype "passive"))
      (node (ref "C14") (pin "P$2") (pinfunction "2_P$2") (pintype "passive"))
      (node (ref "C15") (pin "P$2") (pinfunction "2_P$2") (pintype "passive"))
      (node (ref "C16") (pin "P$2") (pinfunction "2_P$2") (pintype "passive"))
      (node (ref "C17") (pin "P$2") (pinfunction "2_P$2") (pintype "passive"))
      (node (ref "C18") (pin "P$2") (pinfunction "2_P$2") (pintype "passive"))
      (node (ref "C2") (pin "P$2") (pinfunction "2_P$2") (pintype "passive"))
      (node (ref "C3") (pin "P$2") (pinfunction "2_P$2") (pintype "passive"))
      (node (ref "C4") (pin "P$2") (pinfunction "2_P$2") (pintype "passive"))
      (node (ref "C5") (pin "P$2") (pinfunction "2_P$2") (pintype "passive"))
      (node (ref "C6") (pin "P$2") (pinfunction "2_P$2") (pintype "passive"))
      (node (ref "C7") (pin "P$2") (pinfunction "2_P$2") (pintype "passive"))
      (node (ref "C8") (pin "P$2") (pinfunction "2_P$2") (pintype "passive"))
      (node (ref "C9") (pin "P$2") (pinfunction "2_P$2") (pintype "passive"))
      (node (ref "J1") (pin "1") (pinfunction "1_1") (pintype "passive"))
      (node (ref "J2") (pin "1") (pinfunction "1_1") (pintype "passive"))
      (node (ref "J3") (pin "1") (pinfunction "GND_1") (pintype "power_in"))
      (node (ref "J4") (pin "1") (pinfunction "GND_1") (pintype "power_in"))
      (node (ref "J5") (pin "1") (pinfunction "1_1") (pintype "passive"))
      (node (ref "Q1") (pin "1") (pinfunction "G_1") (pintype "passive"))
      (node (ref "Q2") (pin "2") (pinfunction "E_2") (pintype "passive"))
      (node (ref "R16") (pin "P$2") (pinfunction "2_P$2") (pintype "passive"))
      (node (ref "R17") (pin "P$2") (pinfunction "2_P$2") (pintype "passive"))
      (node (ref "R7") (pin "P$1") (pinfunction "1_P$1") (pintype "passive"))
      (node (ref "R8") (pin "P$1") (pinfunction "1_P$1") (pintype "passive"))
      (node (ref "S1") (pin "1") (pinfunction "1_1") (pintype "bidirectional"))
      (node (ref "S1") (pin "2") (pinfunction "1_2") (pintype "bidirectional"))
      (node (ref "S2") (pin "1") (pinfunction "1_1") (pintype "bidirectional"))
      (node (ref "S2") (pin "2") (pinfunction "1_2") (pintype "bidirectional"))
      (node (ref "U1") (pin "2") (pinfunction "GND_2") (pintype "power_in"))
      (node (ref "U10") (pin "1") (pinfunction "GND_1") (pintype "passive"))
      (node (ref "U10") (pin "5") (pinfunction "ADDR_5") (pintype "input"))
      (node (ref "U10") (pin "7") (pinfunction "GND_7") (pintype "passive"))
      (node (ref "U11") (pin "2") (pinfunction "GND_2") (pintype "power_in"))
      (node (ref "U2") (pin "2") (pinfunction "GND_2") (pintype "power_in"))
      (node (ref "U2") (pin "5") (pinfunction "GND_5") (pintype "power_in"))
      (node (ref "U3") (pin "2") (pinfunction "GND_2") (pintype "power_in"))
      (node (ref "U4") (pin "10") (pinfunction "GND_10") (pintype "power_in"))
      (node (ref "U4") (pin "28") (pinfunction "GND_28") (pintype "power_in"))
      (node (ref "U4") (pin "33") (pinfunction "GND_33") (pintype "power_in"))
      (node (ref "U5") (pin "1") (pinfunction "GND_1") (pintype "power_in"))
      (node (ref "U5") (pin "10") (pinfunction "GND_10") (pintype "power_in"))
      (node (ref "U5") (pin "8") (pinfunction "GND_8") (pintype "power_in"))
      (node (ref "U6") (pin "4") (pinfunction "VSS_4") (pintype "power_in"))
      (node (ref "U6") (pin "7") (pinfunction "WP_7") (pintype "input"))
      (node (ref "U7") (pin "1") (pinfunction "ADDR_1") (pintype "input"))
      (node (ref "U7") (pin "4") (pinfunction "GND_4") (pintype "passive"))
      (node (ref "U7") (pin "8") (pinfunction "GND_8") (pintype "passive"))
      (node (ref "U7") (pin "9") (pinfunction "GND_9") (pintype "passive"))
      (node (ref "U8") (pin "3") (pinfunction "GND_3") (pintype "passive"))
      (node (ref "U9") (pin "2") (pinfunction "GND_2") (pintype "power_in"))
    )
    (net (code "17") (name "LED_G") (class "Default")
      (node (ref "A2") (pin "2") (pinfunction "LED_G_2") (pintype "bidirectional"))
      (node (ref "D3") (pin "2") (pinfunction "A_GREEN_2") (pintype "passive"))
      (node (ref "U4") (pin "27") (pinfunction "PA28_27") (pintype "bidirectional"))
    )
    (net (code "18") (name "LED_R") (class "Default")
      (node (ref "A2") (pin "1") (pinfunction "LED_R_1") (pintype "bidirectional"))
      (node (ref "D3") (pin "4") (pinfunction "A_RED_4") (pintype "passive"))
      (node (ref "U4") (pin "25") (pinfunction "PA27_25") (pintype "bidirectional"))
    )
    (net (code "19") (name "LORA_D0") (class "Default")
      (node (ref "U4") (pin "11") (pinfunction "PA08_11") (pintype "bidirectional"))
      (node (ref "U5") (pin "14") (pinfunction "DIO0_14") (pintype "bidirectional"))
    )
    (net (code "20") (name "LORA_D1") (class "Default")
      (node (ref "U4") (pin "12") (pinfunction "PA09_12") (pintype "bidirectional"))
      (node (ref "U5") (pin "15") (pinfunction "DIO1_15") (pintype "bidirectional"))
    )
    (net (code "21") (name "LORA_RST") (class "Default")
      (node (ref "U4") (pin "8") (pinfunction "PA07_8") (pintype "bidirectional"))
      (node (ref "U5") (pin "6") (pinfunction "NRESET_6") (pintype "input"))
    )
    (net (code "22") (name "LORA_SS") (class "Default")
      (node (ref "U4") (pin "7") (pinfunction "PA06_7") (pintype "bidirectional"))
      (node (ref "U5") (pin "5") (pinfunction "NSS_5") (pintype "input"))
    )
    (net (code "23") (name "MCLK") (class "Default")
      (node (ref "A2") (pin "11") (pinfunction "MCLK_11") (pintype "bidirectional"))
      (node (ref "J5") (pin "7") (pinfunction "7_7") (pintype "passive"))
      (node (ref "U4") (pin "20") (pinfunction "PA19_20") (pintype "bidirectional"))
      (node (ref "U5") (pin "4") (pinfunction "SCK_4") (pintype "input"))
    )
    (net (code "24") (name "MISO") (class "Default")
      (node (ref "A2") (pin "12") (pinfunction "MISO_12") (pintype "bidirectional"))
      (node (ref "J5") (pin "6") (pinfunction "6_6") (pintype "passive"))
      (node (ref "U4") (pin "21") (pinfunction "PA22_21") (pintype "bidirectional"))
      (node (ref "U5") (pin "2") (pinfunction "MISO_2") (pintype "output"))
    )
    (net (code "25") (name "MOSI") (class "Default")
      (node (ref "A2") (pin "10") (pinfunction "MOSI_10") (pintype "bidirectional"))
      (node (ref "J5") (pin "8") (pinfunction "8_8") (pintype "passive"))
      (node (ref "U4") (pin "19") (pinfunction "PA18_19") (pintype "bidirectional"))
      (node (ref "U5") (pin "3") (pinfunction "MOSI_3") (pintype "input"))
    )
    (net (code "26") (name "Net-(A1-G16)") (class "Default")
      (node (ref "A1") (pin "1") (pinfunction "~{RST}_1") (pintype "input"))
      (node (ref "A1") (pin "4") (pinfunction "G16_4") (pintype "bidirectional"))
    )
    (net (code "27") (name "Net-(C17-1)") (class "Default")
      (node (ref "C17") (pin "P$1") (pinfunction "1_P$1") (pintype "passive"))
      (node (ref "JP1") (pin "1") (pinfunction "1_1") (pintype "passive"))
      (node (ref "U9") (pin "1") (pinfunction "VDD_1") (pintype "power_in"))
    )
    (net (code "28") (name "Net-(D3-C_GREEN)") (class "Default")
      (node (ref "D3") (pin "3") (pinfunction "C_GREEN_3") (pintype "passive"))
      (node (ref "R17") (pin "P$1") (pinfunction "1_P$1") (pintype "passive"))
    )
    (net (code "29") (name "Net-(D3-C_RED)") (class "Default")
      (node (ref "D3") (pin "1") (pinfunction "C_RED_1") (pintype "passive"))
      (node (ref "R16") (pin "P$1") (pinfunction "1_P$1") (pintype "passive"))
    )
    (net (code "30") (name "Net-(J4-ESP_RX)") (class "Default")
      (node (ref "D2") (pin "C") (pinfunction "C_C") (pintype "passive"))
      (node (ref "J4") (pin "3") (pinfunction "ESP_RX_3") (pintype "bidirectional"))
    )
    (net (code "31") (name "Net-(J4-ESP_TX)") (class "Default")
      (node (ref "J4") (pin "2") (pinfunction "ESP_TX_2") (pintype "power_in"))
      (node (ref "R15") (pin "P$1") (pinfunction "1_P$1") (pintype "passive"))
    )
    (net (code "32") (name "Net-(Q1-D)") (class "Default")
      (node (ref "J2") (pin "2") (pinfunction "2_2") (pintype "passive"))
      (node (ref "Q1") (pin "3") (pinfunction "D_3") (pintype "passive"))
    )
    (net (code "33") (name "Net-(Q2-C)") (class "Default")
      (node (ref "D1") (pin "A") (pinfunction "A_A") (pintype "passive"))
      (node (ref "LS1") (pin "2") (pinfunction "2_2") (pintype "passive"))
      (node (ref "Q2") (pin "3") (pinfunction "C_3") (pintype "passive"))
    )
    (net (code "34") (name "Net-(U3-SW)") (class "Default")
      (node (ref "L1") (pin "2") (pinfunction "2_2") (pintype "passive"))
      (node (ref "U3") (pin "1") (pinfunction "SW_1") (pintype "power_in"))
    )
    (net (code "35") (name "Net-(U5-ANT)") (class "Default")
      (node (ref "AE1") (pin "ANT") (pinfunction "ANT_ANT") (pintype "input"))
      (node (ref "U5") (pin "9") (pinfunction "ANT_9") (pintype "output"))
    )
    (net (code "36") (name "Net-(U8-OUT)") (class "Default")
      (node (ref "JP2") (pin "1") (pinfunction "1_1") (pintype "passive"))
      (node (ref "U8") (pin "2") (pinfunction "OUT_2") (pintype "output"))
    )
    (net (code "37") (name "RESET") (class "Default")
      (node (ref "A2") (pin "16") (pinfunction "RESET_16") (pintype "bidirectional"))
      (node (ref "J5") (pin "2") (pinfunction "2_2") (pintype "passive"))
      (node (ref "R1") (pin "P$1") (pinfunction "1_P$1") (pintype "passive"))
      (node (ref "S1") (pin "3") (pinfunction "2_3") (pintype "bidirectional"))
      (node (ref "S1") (pin "4") (pinfunction "2_4") (pintype "bidirectional"))
      (node (ref "U4") (pin "26") (pinfunction "~{RESET}_26") (pintype "bidirectional"))
    )
    (net (code "38") (name "RX1") (class "Default")
      (node (ref "R12") (pin "P$1") (pinfunction "1_P$1") (pintype "passive"))
      (node (ref "U4") (pin "14") (pinfunction "PA11_14") (pintype "bidirectional"))
    )
    (net (code "39") (name "SCL") (class "Default")
      (node (ref "A2") (pin "7") (pinfunction "SCL_7") (pintype "bidirectional"))
      (node (ref "J5") (pin "9") (pinfunction "9_9") (pintype "passive"))
      (node (ref "R9") (pin "P$1") (pinfunction "1_P$1") (pintype "passive"))
      (node (ref "U10") (pin "4") (pinfunction "SCL_4") (pintype "bidirectional"))
      (node (ref "U11") (pin "6") (pinfunction "SCL_6") (pintype "input"))
      (node (ref "U4") (pin "18") (pinfunction "PA17_18") (pintype "bidirectional"))
      (node (ref "U6") (pin "6") (pinfunction "SCL_6") (pintype "input"))
      (node (ref "U7") (pin "12") (pinfunction "SCL_12") (pintype "bidirectional"))
      (node (ref "U9") (pin "4") (pinfunction "SCL_4") (pintype "input"))
    )
    (net (code "40") (name "SDA") (class "Default")
      (node (ref "A2") (pin "6") (pinfunction "SDA_6") (pintype "bidirectional"))
      (node (ref "J5") (pin "10") (pinfunction "10_10") (pintype "passive"))
      (node (ref "R10") (pin "P$1") (pinfunction "1_P$1") (pintype "passive"))
      (node (ref "U10") (pin "3") (pinfunction "SDA_3") (pintype "bidirectional"))
      (node (ref "U11") (pin "1") (pinfunction "SDA_1") (pintype "bidirectional"))
      (node (ref "U4") (pin "17") (pinfunction "PA16_17") (pintype "bidirectional"))
      (node (ref "U6") (pin "5") (pinfunction "SDA_5") (pintype "bidirectional"))
      (node (ref "U7") (pin "2") (pinfunction "SDA_2") (pintype "bidirectional"))
      (node (ref "U9") (pin "3") (pinfunction "SDA_3") (pintype "bidirectional"))
    )
    (net (code "41") (name "SENSE") (class "Default")
      (node (ref "A2") (pin "4") (pinfunction "SENSE_4") (pintype "bidirectional"))
      (node (ref "J5") (pin "12") (pinfunction "12_12") (pintype "passive"))
      (node (ref "R4") (pin "P$1") (pinfunction "1_P$1") (pintype "passive"))
      (node (ref "U4") (pin "4") (pinfunction "PA03_4") (pintype "bidirectional"))
    )
    (net (code "42") (name "SWCLK{slash}TX3") (class "Default")
      (node (ref "J3") (pin "4") (pinfunction "SWCLK_4") (pintype "output"))
      (node (ref "R13") (pin "P$1") (pinfunction "1_P$1") (pintype "passive"))
      (node (ref "R3") (pin "P$1") (pinfunction "1_P$1") (pintype "passive"))
      (node (ref "U4") (pin "31") (pinfunction "PA30_31") (pintype "bidirectional"))
    )
    (net (code "43") (name "SWDIO{slash}RX3") (class "Default")
      (node (ref "J3") (pin "3") (pinfunction "SWDIO_3") (pintype "bidirectional"))
      (node (ref "JP2") (pin "2") (pinfunction "2_2") (pintype "passive"))
      (node (ref "R14") (pin "P$1") (pinfunction "1_P$1") (pintype "passive"))
      (node (ref "U4") (pin "32") (pinfunction "PA31_32") (pintype "bidirectional"))
    )
    (net (code "44") (name "TX1") (class "Default")
      (node (ref "R11") (pin "P$1") (pinfunction "1_P$1") (pintype "passive"))
      (node (ref "U4") (pin "13") (pinfunction "PA10_13") (pintype "bidirectional"))
    )
    (net (code "45") (name "USB_DM") (class "Default")
      (node (ref "J1") (pin "3") (pinfunction "3_3") (pintype "passive"))
      (node (ref "U4") (pin "23") (pinfunction "PA24_23") (pintype "bidirectional"))
    )
    (net (code "46") (name "USB_DP") (class "Default")
      (node (ref "J1") (pin "2") (pinfunction "2_2") (pintype "passive"))
      (node (ref "U4") (pin "24") (pinfunction "PA25_24") (pintype "bidirectional"))
    )
    (net (code "47") (name "VAUX") (class "Default")
      (node (ref "A1") (pin "8") (pinfunction "VDD_8") (pintype "bidirectional"))
      (node (ref "C8") (pin "P$1") (pinfunction "1_P$1") (pintype "passive"))
      (node (ref "C9") (pin "P$1") (pinfunction "1_P$1") (pintype "passive"))
      (node (ref "R5") (pin "P$1") (pinfunction "1_P$1") (pintype "passive"))
      (node (ref "R6") (pin "P$1") (pinfunction "1_P$1") (pintype "passive"))
      (node (ref "U2") (pin "1") (pinfunction "VOUT_1") (pintype "power_in"))
    )
    (net (code "48") (name "VBAT") (class "Default")
      (node (ref "C10") (pin "P$1") (pinfunction "1_P$1") (pintype "passive"))
      (node (ref "L1") (pin "1") (pinfunction "1_1") (pintype "passive"))
      (node (ref "Q1") (pin "2") (pinfunction "S_2") (pintype "passive"))
      (node (ref "R2") (pin "P$2") (pinfunction "2_P$2") (pintype "passive"))
    )
    (net (code "49") (name "VDDANA") (class "Default")
      (node (ref "C3") (pin "P$1") (pinfunction "1_P$1") (pintype "passive"))
      (node (ref "C4") (pin "P$1") (pinfunction "1_P$1") (pintype "passive"))
      (node (ref "FB1") (pin "P$1") (pinfunction "1_P$1") (pintype "passive"))
      (node (ref "U4") (pin "9") (pinfunction "VDDANA_9") (pintype "power_in"))
    )
    (net (code "50") (name "VDDCORE") (class "Default")
      (node (ref "C6") (pin "P$1") (pinfunction "1_P$1") (pintype "passive"))
      (node (ref "U4") (pin "29") (pinfunction "VDDCORE_29") (pintype "output"))
    )
    (net (code "51") (name "XI32") (class "Default")
      (node (ref "C2") (pin "P$1") (pinfunction "1_P$1") (pintype "passive"))
      (node (ref "U4") (pin "1") (pinfunction "PA00_1") (pintype "bidirectional"))
      (node (ref "Y1") (pin "P$1") (pinfunction "1_P$1") (pintype "bidirectional"))
    )
    (net (code "52") (name "XO32") (class "Default")
      (node (ref "C5") (pin "P$1") (pinfunction "1_P$1") (pintype "passive"))
      (node (ref "U4") (pin "2") (pinfunction "PA01_2") (pintype "bidirectional"))
      (node (ref "Y1") (pin "P$2") (pinfunction "2_P$2") (pintype "bidirectional"))
    )
    (net (code "53") (name "unconnected-(A1-ADC-Pad2)") (class "Default")
      (node (ref "A1") (pin "2") (pinfunction "ADC_2") (pintype "bidirectional"))
    )
    (net (code "54") (name "unconnected-(A1-G2-Pad11)") (class "Default")
      (node (ref "A1") (pin "11") (pinfunction "G2_11") (pintype "bidirectional"))
    )
    (net (code "55") (name "unconnected-(A1-G4-Pad13)") (class "Default")
      (node (ref "A1") (pin "13") (pinfunction "G4_13") (pintype "bidirectional"))
    )
    (net (code "56") (name "unconnected-(A1-G12-Pad6)") (class "Default")
      (node (ref "A1") (pin "6") (pinfunction "G12_6") (pintype "bidirectional"))
    )
    (net (code "57") (name "unconnected-(A1-G13-Pad7)") (class "Default")
      (node (ref "A1") (pin "7") (pinfunction "G13_7") (pintype "bidirectional"))
    )
    (net (code "58") (name "unconnected-(A1-G14-Pad5)") (class "Default")
      (node (ref "A1") (pin "5") (pinfunction "G14_5") (pintype "bidirectional"))
    )
    (net (code "59") (name "unconnected-(U5-DIO2-Pad16)") (class "Default")
      (node (ref "U5") (pin "16") (pinfunction "DIO2_16") (pintype "bidirectional"))
    )
    (net (code "60") (name "unconnected-(U5-DIO3-Pad11)") (class "Default")
      (node (ref "U5") (pin "11") (pinfunction "DIO3_11") (pintype "bidirectional"))
    )
    (net (code "61") (name "unconnected-(U5-DIO4-Pad12)") (class "Default")
      (node (ref "U5") (pin "12") (pinfunction "DIO4_12") (pintype "bidirectional"))
    )
    (net (code "62") (name "unconnected-(U5-DIO5-Pad7)") (class "Default")
      (node (ref "U5") (pin "7") (pinfunction "DIO5_7") (pintype "bidirectional"))
    )
    (net (code "63") (name "unconnected-(U7-INT1-Pad5)") (class "Default")
      (node (ref "U7") (pin "5") (pinfunction "INT1_5") (pintype "bidirectional"))
    )
    (net (code "64") (name "unconnected-(U7-INT2-Pad6)") (class "Default")
      (node (ref "U7") (pin "6") (pinfunction "INT2_6") (pintype "bidirectional"))
    )
  )
)
